# Display.net
KiCad netlist of a schematic drawn in Altium Designer
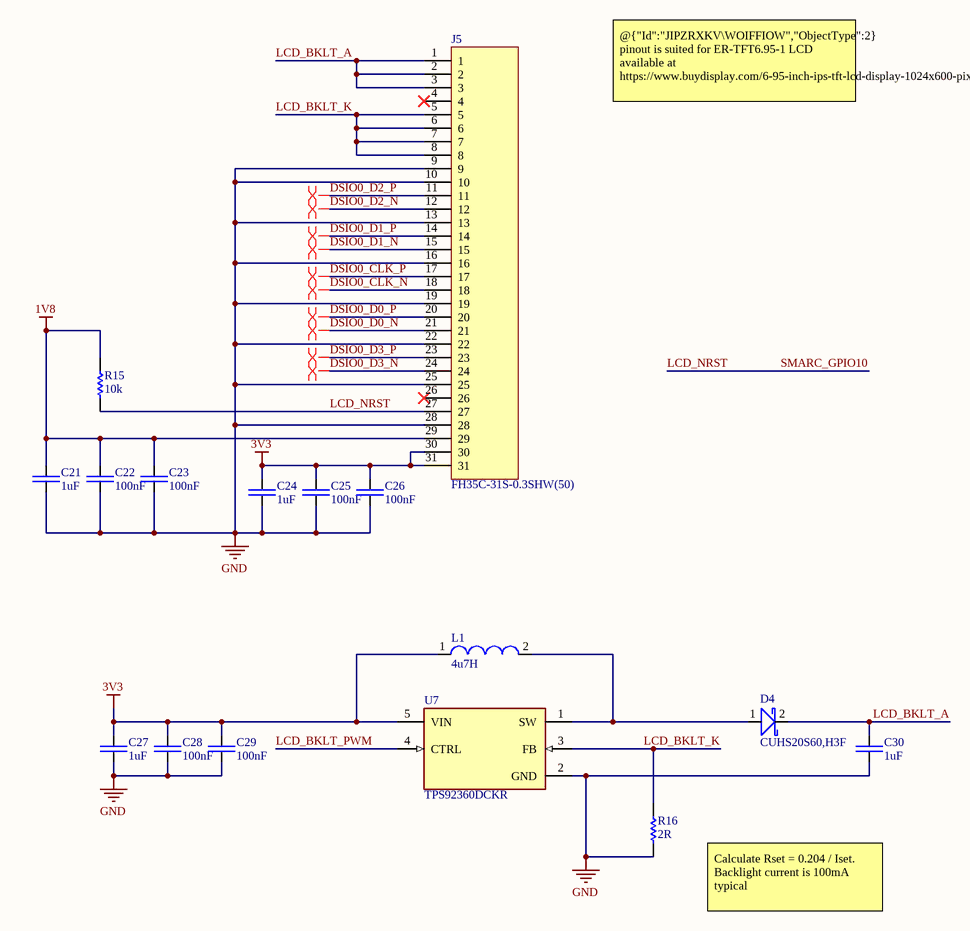
[diagram p0: Display.SchDoc]

(export (version "E")
  (design (tool "Eeschema 10.0.6"))
  (components
    (comp (ref "C21")
      (value "1uF")
      (footprint "CAP-0805")
      (description "Capacitor chip unpolarized. 0805")
      (libsource (lib "Master") (part "CAP-0805"))
    )
    (comp (ref "C22")
      (value "100nF")
      (footprint "CAP-0603")
      (description "Capacitor chip unpolarized. 0603")
      (libsource (lib "Master") (part "CAP-0603"))
    )
    (comp (ref "C23")
      (value "100nF")
      (footprint "CAP-0603")
      (description "Capacitor chip unpolarized. 0603")
      (libsource (lib "Master") (part "CAP-0603"))
    )
    (comp (ref "C24")
      (value "1uF")
      (footprint "CAP-0805")
      (description "Capacitor chip unpolarized. 0805")
      (libsource (lib "Master") (part "CAP-0805"))
    )
    (comp (ref "C25")
      (value "100nF")
      (footprint "CAP-0603")
      (description "Capacitor chip unpolarized. 0603")
      (libsource (lib "Master") (part "CAP-0603"))
    )
    (comp (ref "C26")
      (value "100nF")
      (footprint "CAP-0603")
      (description "Capacitor chip unpolarized. 0603")
      (libsource (lib "Master") (part "CAP-0603"))
    )
    (comp (ref "C27")
      (value "1uF")
      (footprint "CAP-0805")
      (description "Capacitor chip unpolarized. 0805")
      (libsource (lib "Master") (part "CAP-0805"))
    )
    (comp (ref "C28")
      (value "100nF")
      (footprint "CAP-0603")
      (description "Capacitor chip unpolarized. 0603")
      (libsource (lib "Master") (part "CAP-0603"))
    )
    (comp (ref "C29")
      (value "100nF")
      (footprint "CAP-0603")
      (description "Capacitor chip unpolarized. 0603")
      (libsource (lib "Master") (part "CAP-0603"))
    )
    (comp (ref "C30")
      (value "1uF")
      (footprint "CAP-0805")
      (description "Capacitor chip unpolarized. 0805")
      (libsource (lib "Master") (part "CAP-0805"))
    )
    (comp (ref "D4")
      (value "CUHS20S60,H3F")
      (footprint "CUHS20S60,H3F")
      (description "Diode Schottky 2A 0.5V")
      (libsource (lib "Master") (part "CUHS20S60,H3F"))
    )
    (comp (ref "J5")
      (value "FH35C-31S-0.3SHW(50)")
      (footprint "HRS_FH35C-31S-0.3SHW(50)")
      (description "31 Position FPC Connector Contacts, Top and Bottom 0.012 (0.30mm) Surface Mount, Right Angle")
      (fields (field (name "MF") "Hirose Electric"))
      (libsource (lib "Master") (part "FH35C-31S-0.3SHW(50)"))
    )
    (comp (ref "L1") (value "4u7H") (footprint "IND-1210") (libsource (lib "Master") (part "IND-1210")))
    (comp (ref "R15")
      (value "10k")
      (footprint "RES-0603")
      (description "Resistor chip. 0603")
      (libsource (lib "Master") (part "RES-0603"))
    )
    (comp (ref "R16")
      (value "2R")
      (footprint "RES-0603")
      (description "Resistor chip. 0603")
      (libsource (lib "Master") (part "RES-0603"))
    )
    (comp (ref "U7")
      (value "TPS92360DCKR")
      (footprint "FP-DCK0005A-IPC_C")
      (description "38-V 1.2-A single channel LED backlight driver 5-SC70 -40 to 85")
      (libsource (lib "Altium Content Vault") (part "12534fec95d33ffe398d5dc1ac97ce6"))
    )
  )
  (nets
    (net (code "1") (name "/DSIO0_CLK_N") (class "Default")
      (node (ref "J5") (pin "18") (pinfunction "18_18") (pintype "passive"))
    )
    (net (code "2") (name "/DSIO0_CLK_P") (class "Default")
      (node (ref "J5") (pin "17") (pinfunction "17_17") (pintype "passive"))
    )
    (net (code "3") (name "/DSIO0_D0_N") (class "Default")
      (node (ref "J5") (pin "21") (pinfunction "21_21") (pintype "passive"))
    )
    (net (code "4") (name "/DSIO0_D0_P") (class "Default")
      (node (ref "J5") (pin "20") (pinfunction "20_20") (pintype "passive"))
    )
    (net (code "5") (name "/DSIO0_D1_N") (class "Default")
      (node (ref "J5") (pin "15") (pinfunction "15_15") (pintype "passive"))
    )
    (net (code "6") (name "/DSIO0_D1_P") (class "Default")
      (node (ref "J5") (pin "14") (pinfunction "14_14") (pintype "passive"))
    )
    (net (code "7") (name "/DSIO0_D2_N") (class "Default")
      (node (ref "J5") (pin "12") (pinfunction "12_12") (pintype "passive"))
    )
    (net (code "8") (name "/DSIO0_D2_P") (class "Default")
      (node (ref "J5") (pin "11") (pinfunction "11_11") (pintype "passive"))
    )
    (net (code "9") (name "/DSIO0_D3_N") (class "Default")
      (node (ref "J5") (pin "24") (pinfunction "24_24") (pintype "passive"))
    )
    (net (code "10") (name "/DSIO0_D3_P") (class "Default")
      (node (ref "J5") (pin "23") (pinfunction "23_23") (pintype "passive"))
    )
    (net (code "11") (name "/LCD_BKLT_A") (class "Default")
      (node (ref "C30") (pin "2") (pintype "passive"))
      (node (ref "D4") (pin "2") (pintype "passive"))
      (node (ref "J5") (pin "1") (pinfunction "1_1") (pintype "passive"))
      (node (ref "J5") (pin "2") (pinfunction "2_2") (pintype "passive"))
      (node (ref "J5") (pin "3") (pinfunction "3_3") (pintype "passive"))
    )
    (net (code "12") (name "/LCD_BKLT_K") (class "Default")
      (node (ref "J5") (pin "5") (pinfunction "5_5") (pintype "passive"))
      (node (ref "J5") (pin "6") (pinfunction "6_6") (pintype "passive"))
      (node (ref "J5") (pin "7") (pinfunction "7_7") (pintype "passive"))
      (node (ref "J5") (pin "8") (pinfunction "8_8") (pintype "passive"))
      (node (ref "R16") (pin "2") (pintype "passive"))
      (node (ref "U7") (pin "3") (pinfunction "FB_3") (pintype "input"))
    )
    (net (code "13") (name "/LCD_BKLT_PWM") (class "Default")
      (node (ref "U7") (pin "4") (pinfunction "CTRL_4") (pintype "input"))
    )
    (net (code "14") (name "/LCD_NRST") (class "Default")
      (node (ref "J5") (pin "27") (pinfunction "27_27") (pintype "passive"))
      (node (ref "R15") (pin "1") (pintype "passive"))
    )
    (net (code "15") (name "1V8") (class "Default")
      (node (ref "C21") (pin "2") (pintype "passive"))
      (node (ref "C22") (pin "2") (pintype "passive"))
      (node (ref "C23") (pin "2") (pintype "passive"))
      (node (ref "J5") (pin "29") (pinfunction "29_29") (pintype "passive"))
      (node (ref "R15") (pin "2") (pintype "passive"))
    )
    (net (code "16") (name "3V3") (class "Default")
      (node (ref "C24") (pin "2") (pintype "passive"))
      (node (ref "C25") (pin "2") (pintype "passive"))
      (node (ref "C26") (pin "2") (pintype "passive"))
      (node (ref "C27") (pin "2") (pintype "passive"))
      (node (ref "C28") (pin "2") (pintype "passive"))
      (node (ref "C29") (pin "2") (pintype "passive"))
      (node (ref "J5") (pin "30") (pinfunction "30_30") (pintype "passive"))
      (node (ref "J5") (pin "31") (pinfunction "31_31") (pintype "passive"))
      (node (ref "L1") (pin "1") (pintype "passive"))
      (node (ref "U7") (pin "5") (pinfunction "VIN_5") (pintype "power_in"))
    )
    (net (code "17") (name "GND") (class "Default")
      (node (ref "C21") (pin "1") (pintype "passive"))
      (node (ref "C22") (pin "1") (pintype "passive"))
      (node (ref "C23") (pin "1") (pintype "passive"))
      (node (ref "C24") (pin "1") (pintype "passive"))
      (node (ref "C25") (pin "1") (pintype "passive"))
      (node (ref "C26") (pin "1") (pintype "passive"))
      (node (ref "C27") (pin "1") (pintype "passive"))
      (node (ref "C28") (pin "1") (pintype "passive"))
      (node (ref "C29") (pin "1") (pintype "passive"))
      (node (ref "C30") (pin "1") (pintype "passive"))
      (node (ref "J5") (pin "10") (pinfunction "10_10") (pintype "passive"))
      (node (ref "J5") (pin "13") (pinfunction "13_13") (pintype "passive"))
      (node (ref "J5") (pin "16") (pinfunction "16_16") (pintype "passive"))
      (node (ref "J5") (pin "19") (pinfunction "19_19") (pintype "passive"))
      (node (ref "J5") (pin "22") (pinfunction "22_22") (pintype "passive"))
      (node (ref "J5") (pin "25") (pinfunction "25_25") (pintype "passive"))
      (node (ref "J5") (pin "28") (pinfunction "28_28") (pintype "passive"))
      (node (ref "J5") (pin "9") (pinfunction "9_9") (pintype "passive"))
      (node (ref "R16") (pin "1") (pintype "passive"))
      (node (ref "U7") (pin "2") (pinfunction "GND_2") (pintype "power_in"))
    )
    (net (code "18") (name "Net-(U7-SW)") (class "Default")
      (node (ref "D4") (pin "1") (pintype "passive"))
      (node (ref "L1") (pin "2") (pintype "passive"))
      (node (ref "U7") (pin "1") (pinfunction "SW_1") (pintype "passive"))
    )
    (net (code "19") (name "unconnected-(J5-Pad4)") (class "Default")
      (node (ref "J5") (pin "4") (pinfunction "4_4") (pintype "passive+no_connect"))
    )
    (net (code "20") (name "unconnected-(J5-Pad26)") (class "Default")
      (node (ref "J5") (pin "26") (pinfunction "26_26") (pintype "passive+no_connect"))
    )
  )
)
